# m2_connector.net
KiCad netlist of a schematic drawn in Altium Designer
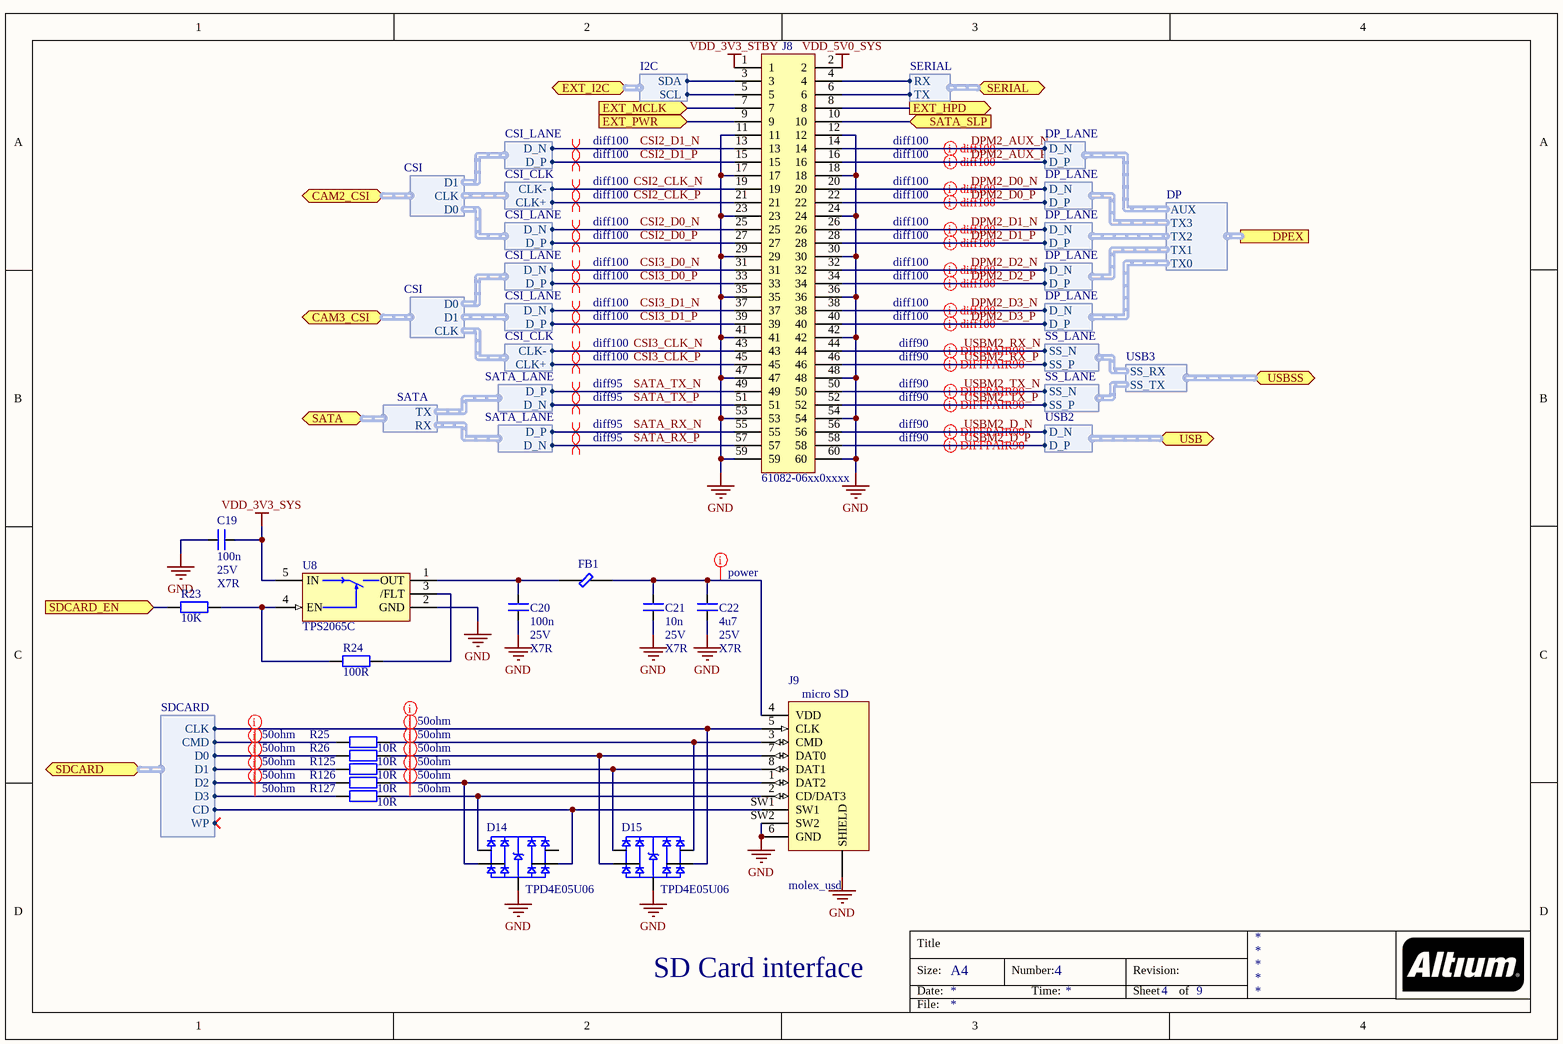
[diagram p0: m2_connector.SchDoc]

(export (version "E")
  (design (tool "Eeschema 10.0.6"))
  (components
    (comp (ref "C19")
      (value "100n")
      (footprint "C1005[0402]")
      (description "Capacitor")
      (fields (field (name "VOLTAGE") "25V") (field (name "TYPE") "X7R") (field (name "Comment") "cap"))
      (libsource (lib "gpa_passives") (part "cap"))
    )
    (comp (ref "C20")
      (value "100n")
      (footprint "C1005[0402]")
      (description "Capacitor")
      (fields (field (name "VOLTAGE") "25V") (field (name "TYPE") "X7R") (field (name "Comment") "cap"))
      (libsource (lib "gpa_passives") (part "cap"))
    )
    (comp (ref "C21")
      (value "10n")
      (footprint "C1005[0402]")
      (description "Capacitor")
      (fields (field (name "VOLTAGE") "25V") (field (name "TYPE") "X7R") (field (name "Comment") "cap"))
      (libsource (lib "gpa_passives") (part "cap"))
    )
    (comp (ref "C22")
      (value "4u7")
      (footprint "C3216[1206]")
      (description "Capacitor")
      (fields (field (name "VOLTAGE") "25V") (field (name "TYPE") "X7R") (field (name "Comment") "cap"))
      (libsource (lib "gpa_passives") (part "cap"))
    )
    (comp (ref "D14")
      (value "TPD4E05U06")
      (footprint "TI_PSON50P100X55-10N")
      (libsource (lib "gpa_ti") (part "tpd4e05u06"))
    )
    (comp (ref "D15")
      (value "TPD4E05U06")
      (footprint "TI_PSON50P100X55-10N")
      (libsource (lib "gpa_ti") (part "tpd4e05u06"))
    )
    (comp (ref "FB1")
      (value "2506036007Y3")
      (footprint "FBC1608X07N")
      (description "Ferrite bead")
      (libsource (lib "gpa_passives") (part "ferrite_bead"))
    )
    (comp (ref "J8")
      (value "61082-06xx0xxxx")
      (footprint "fci_mezzanine_61082")
      (libsource (lib "gpa_connectors") (part "mezzanine_2x30"))
    )
    (comp (ref "J9")
      (value "molex_usd")
      (footprint "molex_usd")
      (libsource (lib "gpa_connectors") (part "molex_usd"))
    )
    (comp (ref "R23")
      (value "10K")
      (footprint "R1005[0402]")
      (description "Resistor")
      (fields (field (name "Comment") "res"))
      (libsource (lib "gpa_passives") (part "res"))
    )
    (comp (ref "R24")
      (value "100R")
      (footprint "R1005[0402]")
      (description "Resistor")
      (fields (field (name "Comment") "res"))
      (libsource (lib "gpa_passives") (part "res"))
    )
    (comp (ref "R25")
      (value "10R")
      (footprint "R1005[0402]")
      (description "Resistor")
      (fields (field (name "Comment") "res"))
      (libsource (lib "gpa_passives") (part "res"))
    )
    (comp (ref "R26")
      (value "10R")
      (footprint "R1005[0402]")
      (description "Resistor")
      (fields (field (name "Comment") "res"))
      (libsource (lib "gpa_passives") (part "res"))
    )
    (comp (ref "R125")
      (value "10R")
      (footprint "R1005[0402]")
      (description "Resistor")
      (fields (field (name "Comment") "res"))
      (libsource (lib "gpa_passives") (part "res"))
    )
    (comp (ref "R126")
      (value "10R")
      (footprint "R1005[0402]")
      (description "Resistor")
      (fields (field (name "Comment") "res"))
      (libsource (lib "gpa_passives") (part "res"))
    )
    (comp (ref "R127")
      (value "10R")
      (footprint "R1005[0402]")
      (description "Resistor")
      (fields (field (name "Comment") "res"))
      (libsource (lib "gpa_passives") (part "res"))
    )
    (comp (ref "U8")
      (value "TPS2065C")
      (footprint "TI_SOT95P280X145-5N")
      (libsource (lib "gpa_ti") (part "tps2065c"))
    )
  )
  (nets
    (net (code "18") (name "/CD") (class "Default")
      (node (ref "D14") (pin "4") (pinfunction "D2-_4") (pintype "passive"))
      (node (ref "J9") (pin "SW1") (pinfunction "SW1_SW1") (pintype "passive"))
    )
    (net (code "19") (name "/CMD") (class "Default")
      (node (ref "R25") (pin "1") (pinfunction "1_1") (pintype "passive"))
    )
    (net (code "20") (name "/CSI2_CLK_N") (class "Default")
      (node (ref "J8") (pin "19") (pinfunction "19_19") (pintype "passive"))
    )
    (net (code "21") (name "/CSI2_CLK_P") (class "Default")
      (node (ref "J8") (pin "21") (pinfunction "21_21") (pintype "passive"))
    )
    (net (code "22") (name "/CSI2_D0_N") (class "Default")
      (node (ref "J8") (pin "25") (pinfunction "25_25") (pintype "passive"))
    )
    (net (code "23") (name "/CSI2_D0_P") (class "Default")
      (node (ref "J8") (pin "27") (pinfunction "27_27") (pintype "passive"))
    )
    (net (code "24") (name "/CSI2_D1_N") (class "Default")
      (node (ref "J8") (pin "13") (pinfunction "13_13") (pintype "passive"))
    )
    (net (code "25") (name "/CSI2_D1_P") (class "Default")
      (node (ref "J8") (pin "15") (pinfunction "15_15") (pintype "passive"))
    )
    (net (code "26") (name "/CSI3_CLK_N") (class "Default")
      (node (ref "J8") (pin "43") (pinfunction "43_43") (pintype "passive"))
    )
    (net (code "27") (name "/CSI3_CLK_P") (class "Default")
      (node (ref "J8") (pin "45") (pinfunction "45_45") (pintype "passive"))
    )
    (net (code "28") (name "/CSI3_D0_N") (class "Default")
      (node (ref "J8") (pin "31") (pinfunction "31_31") (pintype "passive"))
    )
    (net (code "29") (name "/CSI3_D0_P") (class "Default")
      (node (ref "J8") (pin "33") (pinfunction "33_33") (pintype "passive"))
    )
    (net (code "30") (name "/CSI3_D1_N") (class "Default")
      (node (ref "J8") (pin "37") (pinfunction "37_37") (pintype "passive"))
    )
    (net (code "31") (name "/CSI3_D1_P") (class "Default")
      (node (ref "J8") (pin "39") (pinfunction "39_39") (pintype "passive"))
    )
    (net (code "32") (name "/D2") (class "Default")
      (node (ref "R126") (pin "1") (pinfunction "1_1") (pintype "passive"))
    )
    (net (code "33") (name "/D3") (class "Default")
      (node (ref "R127") (pin "1") (pinfunction "1_1") (pintype "passive"))
    )
    (net (code "35") (name "/DPM2_AUX_N") (class "Default")
      (node (ref "J8") (pin "14") (pinfunction "14_14") (pintype "passive"))
    )
    (net (code "36") (name "/DPM2_AUX_P") (class "Default")
      (node (ref "J8") (pin "16") (pinfunction "16_16") (pintype "passive"))
    )
    (net (code "37") (name "/DPM2_D0_N") (class "Default")
      (node (ref "J8") (pin "20") (pinfunction "20_20") (pintype "passive"))
    )
    (net (code "38") (name "/DPM2_D0_P") (class "Default")
      (node (ref "J8") (pin "22") (pinfunction "22_22") (pintype "passive"))
    )
    (net (code "39") (name "/DPM2_D1_N") (class "Default")
      (node (ref "J8") (pin "26") (pinfunction "26_26") (pintype "passive"))
    )
    (net (code "40") (name "/DPM2_D1_P") (class "Default")
      (node (ref "J8") (pin "28") (pinfunction "28_28") (pintype "passive"))
    )
    (net (code "41") (name "/DPM2_D2_N") (class "Default")
      (node (ref "J8") (pin "32") (pinfunction "32_32") (pintype "passive"))
    )
    (net (code "42") (name "/DPM2_D2_P") (class "Default")
      (node (ref "J8") (pin "34") (pinfunction "34_34") (pintype "passive"))
    )
    (net (code "43") (name "/DPM2_D3_N") (class "Default")
      (node (ref "J8") (pin "38") (pinfunction "38_38") (pintype "passive"))
    )
    (net (code "44") (name "/DPM2_D3_P") (class "Default")
      (node (ref "J8") (pin "40") (pinfunction "40_40") (pintype "passive"))
    )
    (net (code "45") (name "/EXT_HPD") (class "Default")
      (node (ref "J8") (pin "8") (pinfunction "8_8") (pintype "passive"))
    )
    (net (code "46") (name "/EXT_MCLK") (class "Default")
      (node (ref "J8") (pin "7") (pinfunction "7_7") (pintype "passive"))
    )
    (net (code "47") (name "/EXT_PWR") (class "Default")
      (node (ref "J8") (pin "9") (pinfunction "9_9") (pintype "passive"))
    )
    (net (code "48") (name "/SATA_RX_N") (class "Default")
      (node (ref "J8") (pin "55") (pinfunction "55_55") (pintype "passive"))
    )
    (net (code "49") (name "/SATA_RX_P") (class "Default")
      (node (ref "J8") (pin "57") (pinfunction "57_57") (pintype "passive"))
    )
    (net (code "50") (name "/SATA_SLP") (class "Default")
      (node (ref "J8") (pin "10") (pinfunction "10_10") (pintype "passive"))
    )
    (net (code "51") (name "/SATA_TX_N") (class "Default")
      (node (ref "J8") (pin "49") (pinfunction "49_49") (pintype "passive"))
    )
    (net (code "52") (name "/SATA_TX_P") (class "Default")
      (node (ref "J8") (pin "51") (pinfunction "51_51") (pintype "passive"))
    )
    (net (code "54") (name "/SCL") (class "Default")
      (node (ref "J8") (pin "5") (pinfunction "5_5") (pintype "passive"))
    )
    (net (code "55") (name "/SDA") (class "Default")
      (node (ref "J8") (pin "3") (pinfunction "3_3") (pintype "passive"))
    )
    (net (code "56") (name "/SDCARD_EN") (class "Default")
      (node (ref "R23") (pin "1") (pinfunction "1_1") (pintype "passive"))
    )
    (net (code "57") (name "/USBM2_D_N") (class "Default")
      (node (ref "J8") (pin "56") (pinfunction "56_56") (pintype "passive"))
    )
    (net (code "58") (name "/USBM2_D_P") (class "Default")
      (node (ref "J8") (pin "58") (pinfunction "58_58") (pintype "passive"))
    )
    (net (code "59") (name "/USBM2_RX_N") (class "Default")
      (node (ref "J8") (pin "44") (pinfunction "44_44") (pintype "passive"))
    )
    (net (code "60") (name "/USBM2_RX_P") (class "Default")
      (node (ref "J8") (pin "46") (pinfunction "46_46") (pintype "passive"))
    )
    (net (code "61") (name "/USBM2_TX_N") (class "Default")
      (node (ref "J8") (pin "50") (pinfunction "50_50") (pintype "passive"))
    )
    (net (code "62") (name "/USBM2_TX_P") (class "Default")
      (node (ref "J8") (pin "52") (pinfunction "52_52") (pintype "passive"))
    )
    (net (code "74") (name "GND") (class "Default")
      (node (ref "C19") (pin "2") (pinfunction "2_2") (pintype "passive"))
      (node (ref "C20") (pin "1") (pinfunction "1_1") (pintype "passive"))
      (node (ref "C21") (pin "1") (pinfunction "1_1") (pintype "passive"))
      (node (ref "C22") (pin "1") (pinfunction "1_1") (pintype "passive"))
      (node (ref "D14") (pin "3") (pinfunction "GND_3") (pintype "passive"))
      (node (ref "D15") (pin "3") (pinfunction "GND_3") (pintype "passive"))
      (node (ref "J8") (pin "11") (pinfunction "11_11") (pintype "passive"))
      (node (ref "J8") (pin "12") (pinfunction "12_12") (pintype "passive"))
      (node (ref "J8") (pin "17") (pinfunction "17_17") (pintype "passive"))
      (node (ref "J8") (pin "18") (pinfunction "18_18") (pintype "passive"))
      (node (ref "J8") (pin "23") (pinfunction "23_23") (pintype "passive"))
      (node (ref "J8") (pin "24") (pinfunction "24_24") (pintype "passive"))
      (node (ref "J8") (pin "29") (pinfunction "29_29") (pintype "passive"))
      (node (ref "J8") (pin "30") (pinfunction "30_30") (pintype "passive"))
      (node (ref "J8") (pin "35") (pinfunction "35_35") (pintype "passive"))
      (node (ref "J8") (pin "36") (pinfunction "36_36") (pintype "passive"))
      (node (ref "J8") (pin "41") (pinfunction "41_41") (pintype "passive"))
      (node (ref "J8") (pin "42") (pinfunction "42_42") (pintype "passive"))
      (node (ref "J8") (pin "47") (pinfunction "47_47") (pintype "passive"))
      (node (ref "J8") (pin "48") (pinfunction "48_48") (pintype "passive"))
      (node (ref "J8") (pin "53") (pinfunction "53_53") (pintype "passive"))
      (node (ref "J8") (pin "54") (pinfunction "54_54") (pintype "passive"))
      (node (ref "J8") (pin "59") (pinfunction "59_59") (pintype "passive"))
      (node (ref "J8") (pin "60") (pinfunction "60_60") (pintype "passive"))
      (node (ref "J9") (pin "6") (pinfunction "GND_6") (pintype "power_in"))
      (node (ref "J9") (pin "SHIELD") (pinfunction "SHIELD_SHIELD") (pintype "passive"))
      (node (ref "J9") (pin "SW2") (pinfunction "SW2_SW2") (pintype "passive"))
      (node (ref "U8") (pin "2") (pinfunction "GND_2") (pintype "power_in"))
    )
    (net (code "75") (name "Net-(D14-D1+)") (class "Default")
      (node (ref "D14") (pin "1") (pinfunction "D1+_1") (pintype "passive"))
      (node (ref "J9") (pin "2") (pinfunction "CD/DAT3_2") (pintype "bidirectional"))
      (node (ref "R127") (pin "2") (pinfunction "2_2") (pintype "passive"))
    )
    (net (code "76") (name "Net-(D14-D1-)") (class "Default")
      (node (ref "D14") (pin "2") (pinfunction "D1-_2") (pintype "passive"))
      (node (ref "J9") (pin "1") (pinfunction "DAT2_1") (pintype "bidirectional"))
      (node (ref "R126") (pin "2") (pinfunction "2_2") (pintype "passive"))
    )
    (net (code "77") (name "Net-(D15-D1+)") (class "Default")
      (node (ref "D15") (pin "1") (pinfunction "D1+_1") (pintype "passive"))
      (node (ref "J9") (pin "8") (pinfunction "DAT1_8") (pintype "bidirectional"))
      (node (ref "R125") (pin "2") (pinfunction "2_2") (pintype "passive"))
    )
    (net (code "78") (name "Net-(D15-D1-)") (class "Default")
      (node (ref "D15") (pin "2") (pinfunction "D1-_2") (pintype "passive"))
      (node (ref "J9") (pin "7") (pinfunction "DAT0_7") (pintype "bidirectional"))
      (node (ref "R26") (pin "2") (pinfunction "2_2") (pintype "passive"))
    )
    (net (code "79") (name "Net-(D15-D2+)") (class "Default")
      (node (ref "D15") (pin "5") (pinfunction "D2+_5") (pintype "passive"))
      (node (ref "J9") (pin "3") (pinfunction "CMD_3") (pintype "bidirectional"))
      (node (ref "R25") (pin "2") (pinfunction "2_2") (pintype "passive"))
    )
    (net (code "80") (name "Net-(D15-D2-)") (class "Default")
      (node (ref "D15") (pin "4") (pinfunction "D2-_4") (pintype "passive"))
      (node (ref "J9") (pin "5") (pinfunction "CLK_5") (pintype "input"))
    )
    (net (code "81") (name "Net-(J9-VDD)") (class "Default")
      (node (ref "C21") (pin "2") (pinfunction "2_2") (pintype "passive"))
      (node (ref "C22") (pin "2") (pinfunction "2_2") (pintype "passive"))
      (node (ref "FB1") (pin "2") (pinfunction "2_2") (pintype "passive"))
      (node (ref "J9") (pin "4") (pinfunction "VDD_4") (pintype "power_in"))
    )
    (net (code "82") (name "Net-(U8-EN)") (class "Default")
      (node (ref "R23") (pin "2") (pinfunction "2_2") (pintype "passive"))
      (node (ref "R24") (pin "1") (pinfunction "1_1") (pintype "passive"))
      (node (ref "U8") (pin "4") (pinfunction "EN_4") (pintype "input"))
    )
    (net (code "83") (name "Net-(U8-OUT)") (class "Default")
      (node (ref "C20") (pin "2") (pinfunction "2_2") (pintype "passive"))
      (node (ref "FB1") (pin "1") (pinfunction "1_1") (pintype "passive"))
      (node (ref "U8") (pin "1") (pinfunction "OUT_1") (pintype "power_in"))
    )
    (net (code "84") (name "Net-(U8-{slash}FLT)") (class "Default")
      (node (ref "R24") (pin "2") (pinfunction "2_2") (pintype "passive"))
      (node (ref "U8") (pin "3") (pinfunction "/FLT_3") (pintype "open_collector"))
    )
    (net (code "85") (name "VDD_3V3_STBY") (class "Default")
      (node (ref "J8") (pin "1") (pinfunction "1_1") (pintype "passive"))
    )
    (net (code "86") (name "VDD_3V3_SYS") (class "Default")
      (node (ref "C19") (pin "1") (pinfunction "1_1") (pintype "passive"))
      (node (ref "U8") (pin "5") (pinfunction "IN_5") (pintype "power_in"))
    )
    (net (code "87") (name "VDD_5V0_SYS") (class "Default")
      (node (ref "J8") (pin "2") (pinfunction "2_2") (pintype "passive"))
    )
    (net (code "88") (name "unconnected-(D14-D2+-Pad5)") (class "Default")
      (node (ref "D14") (pin "5") (pinfunction "D2+_5") (pintype "passive"))
    )
    (net (code "89") (name "unconnected-(J8-Pad4)") (class "Default")
      (node (ref "J8") (pin "4") (pinfunction "4_4") (pintype "passive"))
    )
    (net (code "90") (name "unconnected-(J8-Pad6)") (class "Default")
      (node (ref "J8") (pin "6") (pinfunction "6_6") (pintype "passive"))
    )
    (net (code "91") (name "unconnected-(R26-Pad1)") (class "Default")
      (node (ref "R26") (pin "1") (pinfunction "1_1") (pintype "passive"))
    )
    (net (code "92") (name "unconnected-(R125-Pad1)") (class "Default")
      (node (ref "R125") (pin "1") (pinfunction "1_1") (pintype "passive"))
    )
  )
)
